# Microcontroller.net
KiCad netlist of a schematic drawn in Altium Designer
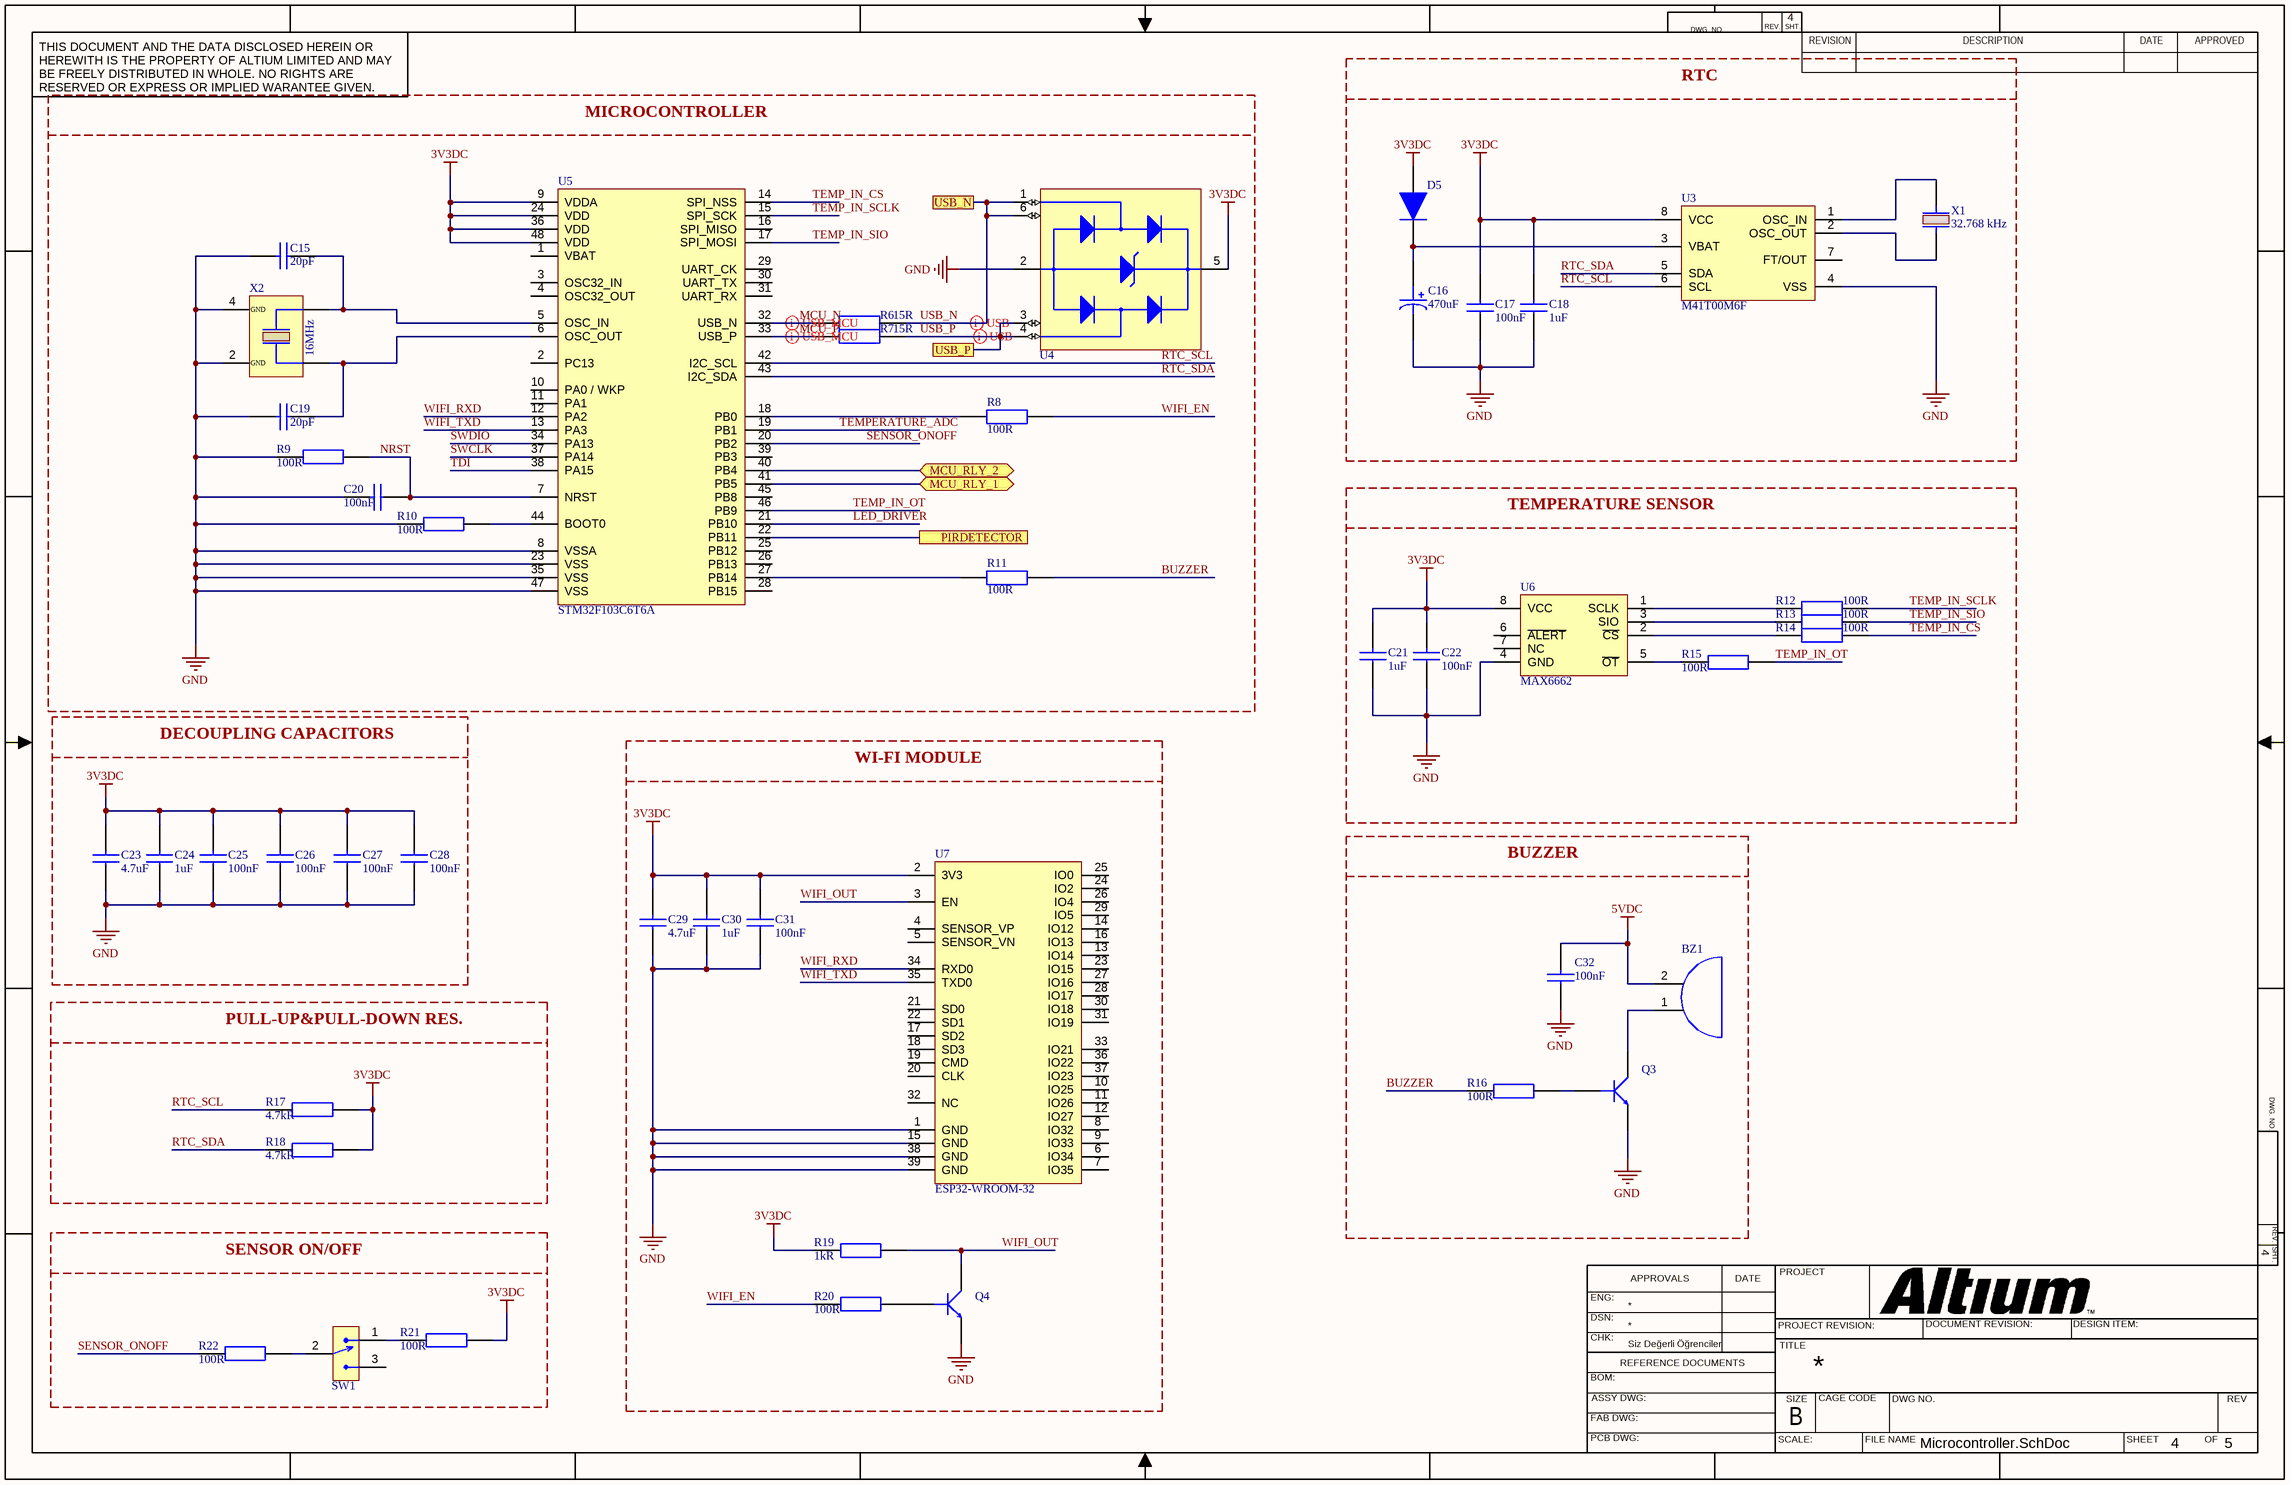
[diagram p0: Microcontroller.SchDoc]

(export (version "E")
  (design (tool "Eeschema 10.0.6"))
  (components
    (comp (ref "BZ1")
      (value "CMI-9605IC-0580T")
      (footprint "CMI-9605IC")
      (description "Buzzers Indicator, Internally Driven Magnetic 5V 30mA 2.7kHz 80dB @ 5V, 10cm Through Hole PC Pins")
      (fields (field (name "MANUFACTURER") "CUI Devices") (field (name "DESIGNED BY") "BERK"))
      (libsource (lib "UDEMY_Library") (part "CMI-9605IC-0580T"))
    )
    (comp (ref "C15")
      (value "CL10C200JB8NNNC")
      (footprint "CAP_0603")
      (description "CAP CER 20pF %5 0603 SMD")
      (fields
        (field (name "MANUFACTURER") "Samsung")
        (field (name "TOLERANCE") "5%")
        (field (name "CAPACITANCE") "20pF")
        (field (name "DESIGNED BY") "BERK")
      )
      (libsource (lib "UDEMY_Library") (part "CAP CER 20pF 0603"))
    )
    (comp (ref "C16")
      (value "ESH477M050AH4AA")
      (footprint "CAP_RADIAL_D10_P5")
      (description "CAP ALU ELEC 470uF 50V RADIAL")
      (fields
        (field (name "MANUFACTURER") "KEMET")
        (field (name "TOLERANCE") "20%")
        (field (name "CAPACITANCE") "470uF")
        (field (name "DESIGNED BY") "BERK")
      )
      (libsource (lib "UDEMY_Library") (part "CAP ALU ELEC 470uF 50V"))
    )
    (comp (ref "C17")
      (value "CL21B104KBCNNNC")
      (footprint "CAP_0805")
      (description "CAP CER 100nF %10 0805")
      (fields
        (field (name "MANUFACTURER") "Samsung")
        (field (name "TOLERANCE") "10%")
        (field (name "CAPACITANCE") "100nF")
        (field (name "DESIGNED BY") "BERK")
      )
      (libsource (lib "UDEMY_Library") (part "CAP CER 100nF 0805"))
    )
    (comp (ref "C18")
      (value "CL21B105KBFNNNE")
      (footprint "CAP_0805")
      (description "CAP CER 1uF %10 0805")
      (fields
        (field (name "MANUFACTURER") "Samsung")
        (field (name "TOLERANCE") "10%")
        (field (name "CAPACITANCE") "1uF")
        (field (name "DESIGNED BY") "BERK")
      )
      (libsource (lib "UDEMY_Library") (part "CAP CER 1uF 0805"))
    )
    (comp (ref "C19")
      (value "CL10C200JB8NNNC")
      (footprint "CAP_0603")
      (description "CAP CER 20pF %5 0603 SMD")
      (fields
        (field (name "MANUFACTURER") "Samsung")
        (field (name "TOLERANCE") "5%")
        (field (name "CAPACITANCE") "20pF")
        (field (name "DESIGNED BY") "BERK")
      )
      (libsource (lib "UDEMY_Library") (part "CAP CER 20pF 0603"))
    )
    (comp (ref "C20")
      (value "C0603C104K5RACTU")
      (footprint "CAP_0603")
      (description "CAP CER 100nF %10 0603 SMD")
      (fields
        (field (name "MANUFACTURER") "KEMET")
        (field (name "TOLERANCE") "10%")
        (field (name "CAPACITANCE") "100nF")
        (field (name "DESIGNED BY") "BERK")
      )
      (libsource (lib "UDEMY_Library") (part "CAP CER 100nF 0603"))
    )
    (comp (ref "C21")
      (value "CL21B105KBFNNNE")
      (footprint "CAP_0805")
      (description "CAP CER 1uF %10 0805")
      (fields
        (field (name "MANUFACTURER") "Samsung")
        (field (name "TOLERANCE") "10%")
        (field (name "CAPACITANCE") "1uF")
        (field (name "DESIGNED BY") "BERK")
      )
      (libsource (lib "UDEMY_Library") (part "CAP CER 1uF 0805"))
    )
    (comp (ref "C22")
      (value "CL21B104KBCNNNC")
      (footprint "CAP_0805")
      (description "CAP CER 100nF %10 0805")
      (fields
        (field (name "MANUFACTURER") "Samsung")
        (field (name "TOLERANCE") "10%")
        (field (name "CAPACITANCE") "100nF")
        (field (name "DESIGNED BY") "BERK")
      )
      (libsource (lib "UDEMY_Library") (part "CAP CER 100nF 0805"))
    )
    (comp (ref "C23")
      (value "CL21A475KAQNNNE")
      (footprint "CAP_0805")
      (description "CAP CER 4.7uF %10 0805")
      (fields
        (field (name "MANUFACTURER") "Samsung")
        (field (name "TOLERANCE") "10%")
        (field (name "CAPACITANCE") "4.7uF")
        (field (name "DESIGNED BY") "BERK")
      )
      (libsource (lib "UDEMY_Library") (part "CAP CER 4.7uF 0805"))
    )
    (comp (ref "C24")
      (value "CL21B105KBFNNNE")
      (footprint "CAP_0805")
      (description "CAP CER 1uF %10 0805")
      (fields
        (field (name "MANUFACTURER") "Samsung")
        (field (name "TOLERANCE") "10%")
        (field (name "CAPACITANCE") "1uF")
        (field (name "DESIGNED BY") "BERK")
      )
      (libsource (lib "UDEMY_Library") (part "CAP CER 1uF 0805"))
    )
    (comp (ref "C25")
      (value "C0603C104K5RACTU")
      (footprint "CAP_0603")
      (description "CAP CER 100nF %10 0603 SMD")
      (fields
        (field (name "MANUFACTURER") "KEMET")
        (field (name "TOLERANCE") "10%")
        (field (name "CAPACITANCE") "100nF")
        (field (name "DESIGNED BY") "BERK")
      )
      (libsource (lib "UDEMY_Library") (part "CAP CER 100nF 0603"))
    )
    (comp (ref "C26")
      (value "C0603C104K5RACTU")
      (footprint "CAP_0603")
      (description "CAP CER 100nF %10 0603 SMD")
      (fields
        (field (name "MANUFACTURER") "KEMET")
        (field (name "TOLERANCE") "10%")
        (field (name "CAPACITANCE") "100nF")
        (field (name "DESIGNED BY") "BERK")
      )
      (libsource (lib "UDEMY_Library") (part "CAP CER 100nF 0603"))
    )
    (comp (ref "C27")
      (value "C0603C104K5RACTU")
      (footprint "CAP_0603")
      (description "CAP CER 100nF %10 0603 SMD")
      (fields
        (field (name "MANUFACTURER") "KEMET")
        (field (name "TOLERANCE") "10%")
        (field (name "CAPACITANCE") "100nF")
        (field (name "DESIGNED BY") "BERK")
      )
      (libsource (lib "UDEMY_Library") (part "CAP CER 100nF 0603"))
    )
    (comp (ref "C28")
      (value "C0603C104K5RACTU")
      (footprint "CAP_0603")
      (description "CAP CER 100nF %10 0603 SMD")
      (fields
        (field (name "MANUFACTURER") "KEMET")
        (field (name "TOLERANCE") "10%")
        (field (name "CAPACITANCE") "100nF")
        (field (name "DESIGNED BY") "BERK")
      )
      (libsource (lib "UDEMY_Library") (part "CAP CER 100nF 0603"))
    )
    (comp (ref "C29")
      (value "CL21A475KAQNNNE")
      (footprint "CAP_0805")
      (description "CAP CER 4.7uF %10 0805")
      (fields
        (field (name "MANUFACTURER") "Samsung")
        (field (name "TOLERANCE") "10%")
        (field (name "CAPACITANCE") "4.7uF")
        (field (name "DESIGNED BY") "BERK")
      )
      (libsource (lib "UDEMY_Library") (part "CAP CER 4.7uF 0805"))
    )
    (comp (ref "C30")
      (value "CL21B105KBFNNNE")
      (footprint "CAP_0805")
      (description "CAP CER 1uF %10 0805")
      (fields
        (field (name "MANUFACTURER") "Samsung")
        (field (name "TOLERANCE") "10%")
        (field (name "CAPACITANCE") "1uF")
        (field (name "DESIGNED BY") "BERK")
      )
      (libsource (lib "UDEMY_Library") (part "CAP CER 1uF 0805"))
    )
    (comp (ref "C31")
      (value "CL21B104KBCNNNC")
      (footprint "CAP_0805")
      (description "CAP CER 100nF %10 0805")
      (fields
        (field (name "MANUFACTURER") "Samsung")
        (field (name "TOLERANCE") "10%")
        (field (name "CAPACITANCE") "100nF")
        (field (name "DESIGNED BY") "BERK")
      )
      (libsource (lib "UDEMY_Library") (part "CAP CER 100nF 0805"))
    )
    (comp (ref "C32")
      (value "CL21B104KBCNNNC")
      (footprint "CAP_0805")
      (description "CAP CER 100nF %10 0805")
      (fields
        (field (name "MANUFACTURER") "Samsung")
        (field (name "TOLERANCE") "10%")
        (field (name "CAPACITANCE") "100nF")
        (field (name "DESIGNED BY") "BERK")
      )
      (libsource (lib "UDEMY_Library") (part "CAP CER 100nF 0805"))
    )
    (comp (ref "D5")
      (value "1N4148WS")
      (footprint "SOD323F")
      (description "Diode, Single, 75 V, 150 mA, 1 V, 4 ns")
      (fields
        (field (name "MANUFACTURER") "ON Semiconductor / Fairchild")
        (field (name "DESIGNED BY") "BERK")
      )
      (libsource (lib "UDEMY_Library") (part "1N4148WS"))
    )
    (comp (ref "Q3")
      (value "MMBT3904-7-F")
      (footprint "SOT-23F")
      (description "Transistor General Purpose BJT NPN 40 Volt 0.2A Automotive 3-Pin SOT-23")
      (fields (field (name "MANUFACTURER") "Diodes Zetex") (field (name "DESIGNED BY") "BERK"))
      (libsource (lib "UDEMY_Library") (part "MMBT3904-7-F"))
    )
    (comp (ref "Q4")
      (value "MMBT3904-7-F")
      (footprint "SOT-23F")
      (description "Transistor General Purpose BJT NPN 40 Volt 0.2A Automotive 3-Pin SOT-23")
      (fields (field (name "MANUFACTURER") "Diodes Zetex") (field (name "DESIGNED BY") "BERK"))
      (libsource (lib "UDEMY_Library") (part "MMBT3904-7-F"))
    )
    (comp (ref "R6")
      (value "RC0603JR-0715RL")
      (footprint "RES_0603")
      (description "RES 15 %5 OHM 0603 SMD")
      (fields
        (field (name "MANUFACTURER") "Yageo")
        (field (name "TOLERANCE") "5%")
        (field (name "RESISTANCE") "15R")
        (field (name "DESIGNED BY") "BERK")
      )
      (libsource (lib "UDEMY_Library") (part "RES 15 OHM 0603"))
    )
    (comp (ref "R7")
      (value "RC0603JR-0715RL")
      (footprint "RES_0603")
      (description "RES 15 %5 OHM 0603 SMD")
      (fields
        (field (name "MANUFACTURER") "Yageo")
        (field (name "TOLERANCE") "5%")
        (field (name "RESISTANCE") "15R")
        (field (name "DESIGNED BY") "BERK")
      )
      (libsource (lib "UDEMY_Library") (part "RES 15 OHM 0603"))
    )
    (comp (ref "R8")
      (value "RC0603JR-07100RL")
      (footprint "RES_0603")
      (description "RES 100 %5 OHM 0603 SMD")
      (fields
        (field (name "MANUFACTURER") "Yageo")
        (field (name "TOLERANCE") "5%")
        (field (name "RESISTANCE") "100R")
        (field (name "DESIGNED BY") "BERK")
      )
      (libsource (lib "UDEMY_Library") (part "RES 100 OHM 0603"))
    )
    (comp (ref "R9")
      (value "RC0603JR-07100RL")
      (footprint "RES_0603")
      (description "RES 100 %5 OHM 0603 SMD")
      (fields
        (field (name "MANUFACTURER") "Yageo")
        (field (name "TOLERANCE") "5%")
        (field (name "RESISTANCE") "100R")
        (field (name "DESIGNED BY") "BERK")
      )
      (libsource (lib "UDEMY_Library") (part "RES 100 OHM 0603"))
    )
    (comp (ref "R10")
      (value "RC0603JR-07100RL")
      (footprint "RES_0603")
      (description "RES 100 %5 OHM 0603 SMD")
      (fields
        (field (name "MANUFACTURER") "Yageo")
        (field (name "TOLERANCE") "5%")
        (field (name "RESISTANCE") "100R")
        (field (name "DESIGNED BY") "BERK")
      )
      (libsource (lib "UDEMY_Library") (part "RES 100 OHM 0603"))
    )
    (comp (ref "R11")
      (value "RC0603JR-07100RL")
      (footprint "RES_0603")
      (description "RES 100 %5 OHM 0603 SMD")
      (fields
        (field (name "MANUFACTURER") "Yageo")
        (field (name "TOLERANCE") "5%")
        (field (name "RESISTANCE") "100R")
        (field (name "DESIGNED BY") "BERK")
      )
      (libsource (lib "UDEMY_Library") (part "RES 100 OHM 0603"))
    )
    (comp (ref "R12")
      (value "RC0603JR-07100RL")
      (footprint "RES_0603")
      (description "RES 100 %5 OHM 0603 SMD")
      (fields
        (field (name "MANUFACTURER") "Yageo")
        (field (name "TOLERANCE") "5%")
        (field (name "RESISTANCE") "100R")
        (field (name "DESIGNED BY") "BERK")
      )
      (libsource (lib "UDEMY_Library") (part "RES 100 OHM 0603"))
    )
    (comp (ref "R13")
      (value "RC0603JR-07100RL")
      (footprint "RES_0603")
      (description "RES 100 %5 OHM 0603 SMD")
      (fields
        (field (name "MANUFACTURER") "Yageo")
        (field (name "TOLERANCE") "5%")
        (field (name "RESISTANCE") "100R")
        (field (name "DESIGNED BY") "BERK")
      )
      (libsource (lib "UDEMY_Library") (part "RES 100 OHM 0603"))
    )
    (comp (ref "R14")
      (value "RC0603JR-07100RL")
      (footprint "RES_0603")
      (description "RES 100 %5 OHM 0603 SMD")
      (fields
        (field (name "MANUFACTURER") "Yageo")
        (field (name "TOLERANCE") "5%")
        (field (name "RESISTANCE") "100R")
        (field (name "DESIGNED BY") "BERK")
      )
      (libsource (lib "UDEMY_Library") (part "RES 100 OHM 0603"))
    )
    (comp (ref "R15")
      (value "RC0603JR-07100RL")
      (footprint "RES_0603")
      (description "RES 100 %5 OHM 0603 SMD")
      (fields
        (field (name "MANUFACTURER") "Yageo")
        (field (name "TOLERANCE") "5%")
        (field (name "RESISTANCE") "100R")
        (field (name "DESIGNED BY") "BERK")
      )
      (libsource (lib "UDEMY_Library") (part "RES 100 OHM 0603"))
    )
    (comp (ref "R16")
      (value "RC0603JR-07100RL")
      (footprint "RES_0603")
      (description "RES 100 %5 OHM 0603 SMD")
      (fields
        (field (name "MANUFACTURER") "Yageo")
        (field (name "TOLERANCE") "5%")
        (field (name "RESISTANCE") "100R")
        (field (name "DESIGNED BY") "BERK")
      )
      (libsource (lib "UDEMY_Library") (part "RES 100 OHM 0603"))
    )
    (comp (ref "R17")
      (value "RC0603JR-074K7L")
      (footprint "RES_0603")
      (description "RES 4K7 %5 OHM 0603 SMD")
      (fields
        (field (name "MANUFACTURER") "Yageo")
        (field (name "TOLERANCE") "5%")
        (field (name "RESISTANCE") "4.7kR")
        (field (name "DESIGNED BY") "BERK")
      )
      (libsource (lib "UDEMY_Library") (part "RES 4K7 OHM 0603"))
    )
    (comp (ref "R18")
      (value "RC0603JR-074K7L")
      (footprint "RES_0603")
      (description "RES 4K7 %5 OHM 0603 SMD")
      (fields
        (field (name "MANUFACTURER") "Yageo")
        (field (name "TOLERANCE") "5%")
        (field (name "RESISTANCE") "4.7kR")
        (field (name "DESIGNED BY") "BERK")
      )
      (libsource (lib "UDEMY_Library") (part "RES 4K7 OHM 0603"))
    )
    (comp (ref "R19")
      (value "RC0603FR-0710KL")
      (footprint "RES_0603")
      (description "RES 1K %1 OHM 0603 SMD")
      (fields
        (field (name "MANUFACTURER") "Yageo")
        (field (name "MANUFACTURER PART NUMBER") "RC0603JR-071KL")
        (field (name "RESISTANCE") "1kR")
        (field (name "DESIGNED BY") "BERK")
      )
      (libsource (lib "UDEMY_Library") (part "RES 1K OHM 0603"))
    )
    (comp (ref "R20")
      (value "RC0603JR-07100RL")
      (footprint "RES_0603")
      (description "RES 100 %5 OHM 0603 SMD")
      (fields
        (field (name "MANUFACTURER") "Yageo")
        (field (name "TOLERANCE") "5%")
        (field (name "RESISTANCE") "100R")
        (field (name "DESIGNED BY") "BERK")
      )
      (libsource (lib "UDEMY_Library") (part "RES 100 OHM 0603"))
    )
    (comp (ref "R21")
      (value "RC0603JR-07100RL")
      (footprint "RES_0603")
      (description "RES 100 %5 OHM 0603 SMD")
      (fields
        (field (name "MANUFACTURER") "Yageo")
        (field (name "TOLERANCE") "5%")
        (field (name "RESISTANCE") "100R")
        (field (name "DESIGNED BY") "BERK")
      )
      (libsource (lib "UDEMY_Library") (part "RES 100 OHM 0603"))
    )
    (comp (ref "R22")
      (value "RC0603JR-07100RL")
      (footprint "RES_0603")
      (description "RES 100 %5 OHM 0603 SMD")
      (fields
        (field (name "MANUFACTURER") "Yageo")
        (field (name "TOLERANCE") "5%")
        (field (name "RESISTANCE") "100R")
        (field (name "DESIGNED BY") "BERK")
      )
      (libsource (lib "") (part "RES 100 OHM 0603_1"))
    )
    (comp (ref "SW1")
      (value "EG1215AA")
      (footprint "EG1215AA")
      (description "Slide Switch, SPDT, 0.025A, 24V, SMD")
      (fields
        (field (name "MANUFACTURER") "E-Switch")
        (field (name "TOLERANCE") "4.95%")
        (field (name "DESIGNED BY") "BERK")
      )
      (libsource (lib "UDEMY_Library") (part "EG1215AA"))
    )
    (comp (ref "U3")
      (value "M41T00M6F")
      (footprint "SOIC8")
      (description "IC RTC CLK/CALENDAR I2C 8-SOIC")
      (fields (field (name "MANUFACTURER") "STMicroelectronics") (field (name "DESIGNED BY") "BERK"))
      (libsource (lib "UDEMY_Library") (part "M41T00M6F"))
    )
    (comp (ref "U4")
      (value "USBLC6-2SC6")
      (footprint "SOT23-6L")
      (description "TVS DIODE 5.25V 17V SOT23-6")
      (fields (field (name "MANUFACTURER") "STMicroelectronics") (field (name "DESIGNED BY") "BERK"))
      (libsource (lib "UDEMY_Library") (part "USB PROTECTION"))
    )
    (comp (ref "U5")
      (value "STM32F103C6T6A")
      (footprint "LQFP-48")
      (description "MCU 32-bit STM32F ARM Cortex M3 RISC 32KB Flash 2.5V/3.3V 48-Pin LQFP Tray")
      (fields (field (name "MANUFACTURER") "STMicroelectronics") (field (name "DESIGNED BY") "BERK"))
      (libsource (lib "UDEMY_Library") (part "STM32F103C6T6A"))
    )
    (comp (ref "U6")
      (value "MAX6662")
      (footprint "SOIC8")
      (description "SENSOR TEMPERATURE SPI 8SOIC")
      (fields
        (field (name "MANUFACTURER") "Maxim")
        (field (name "MANUFACTURER PART NUMBER") "MAX6662MSA+")
        (field (name "DESIGNED BY") "BERK")
      )
      (libsource (lib "UDEMY_Library") (part "MAX6662"))
    )
    (comp (ref "U7")
      (value "ESP32-WROOM-32")
      (footprint "ESP32-32")
      (description "SMD MODULE, ESP32-D0WDQ6, 32MBIT")
      (fields (field (name "MANUFACTURER") "Espressif Systems") (field (name "DESIGNED BY") "BERK"))
      (libsource (lib "UDEMY_Library") (part "ESP32-WROOM-32"))
    )
    (comp (ref "X1")
      (value "ABS05-32.768KHZ-T")
      (footprint "ABS05")
      (description "Crystal, 32.768 kHz, SMD, 1.6mm x 1mm, 12.5 pF, 20 ppm, ABS05 Series")
      (fields
        (field (name "MANUFACTURER") "Abracon")
        (field (name "TOLERANCE") "20ppm")
        (field (name "OPERATING FREQUENCY") "32.768 kHz")
        (field (name "DESIGNED BY") "BERK")
      )
      (libsource (lib "UDEMY_Library") (part "CRYSTAL 32768kHZ"))
    )
    (comp (ref "X2")
      (value "ECS-160-20-30B-TR")
      (footprint "ECS")
      (description "CRYSTAL 16.0000MHZ 20PF SMD")
      (fields
        (field (name "MANUFACTURER") "ECS International")
        (field (name "TOLERANCE") "50ppm")
        (field (name "FREQUENCY") "16MHz")
        (field (name "DESIGNED BY") "BERK")
      )
      (libsource (lib "UDEMY_Library") (part "CRYSTAL 16MHz"))
    )
  )
  (nets
    (net (code "1") (name "/BUZZER") (class "Default")
      (node (ref "R11") (pin "2") (pinfunction "2_2") (pintype "passive"))
      (node (ref "R16") (pin "1") (pinfunction "1_1") (pintype "passive"))
    )
    (net (code "2") (name "/LED_DRIVER") (class "Default")
      (node (ref "U5") (pin "21") (pinfunction "PB10_21") (pintype "passive"))
    )
    (net (code "3") (name "/MCU_N") (class "Default")
      (node (ref "R6") (pin "1") (pinfunction "1_1") (pintype "passive"))
      (node (ref "U5") (pin "32") (pinfunction "USB_N_32") (pintype "passive"))
    )
    (net (code "4") (name "/MCU_P") (class "Default")
      (node (ref "R7") (pin "1") (pinfunction "1_1") (pintype "passive"))
      (node (ref "U5") (pin "33") (pinfunction "USB_P_33") (pintype "passive"))
    )
    (net (code "5") (name "/MCU_RLY_1") (class "Default")
      (node (ref "U5") (pin "41") (pinfunction "PB5_41") (pintype "passive"))
    )
    (net (code "6") (name "/MCU_RLY_2") (class "Default")
      (node (ref "U5") (pin "40") (pinfunction "PB4_40") (pintype "passive"))
    )
    (net (code "7") (name "/NRST") (class "Default")
      (node (ref "C20") (pin "1") (pinfunction "1_1") (pintype "passive"))
      (node (ref "R9") (pin "2") (pinfunction "2_2") (pintype "passive"))
      (node (ref "U5") (pin "7") (pinfunction "NRST_7") (pintype "passive"))
    )
    (net (code "8") (name "/PIRDETECTOR") (class "Default")
      (node (ref "U5") (pin "22") (pinfunction "PB11_22") (pintype "passive"))
    )
    (net (code "9") (name "/RTC_SCL") (class "Default")
      (node (ref "R17") (pin "1") (pinfunction "1_1") (pintype "passive"))
      (node (ref "U3") (pin "6") (pinfunction "SCL_6") (pintype "passive"))
      (node (ref "U5") (pin "42") (pinfunction "I2C_SCL_42") (pintype "passive"))
    )
    (net (code "10") (name "/RTC_SDA") (class "Default")
      (node (ref "R18") (pin "1") (pinfunction "1_1") (pintype "passive"))
      (node (ref "U3") (pin "5") (pinfunction "SDA_5") (pintype "passive"))
      (node (ref "U5") (pin "43") (pinfunction "I2C_SDA_43") (pintype "passive"))
    )
    (net (code "11") (name "/SENSOR_ONOFF") (class "Default")
      (node (ref "R22") (pin "2") (pinfunction "2_2") (pintype "passive"))
      (node (ref "U5") (pin "20") (pinfunction "PB2_20") (pintype "passive"))
    )
    (net (code "12") (name "/SWCLK") (class "Default")
      (node (ref "U5") (pin "37") (pinfunction "PA14_37") (pintype "passive"))
    )
    (net (code "13") (name "/SWDIO") (class "Default")
      (node (ref "U5") (pin "34") (pinfunction "PA13_34") (pintype "passive"))
    )
    (net (code "14") (name "/TDI") (class "Default")
      (node (ref "U5") (pin "38") (pinfunction "PA15_38") (pintype "passive"))
    )
    (net (code "15") (name "/TEMPERATURE_ADC") (class "Default")
      (node (ref "U5") (pin "19") (pinfunction "PB1_19") (pintype "passive"))
    )
    (net (code "16") (name "/TEMP_IN_CS") (class "Default")
      (node (ref "R14") (pin "2") (pinfunction "2_2") (pintype "passive"))
      (node (ref "U5") (pin "14") (pinfunction "SPI_NSS_14") (pintype "passive"))
    )
    (net (code "17") (name "/TEMP_IN_OT") (class "Default")
      (node (ref "R15") (pin "2") (pinfunction "2_2") (pintype "passive"))
      (node (ref "U5") (pin "46") (pinfunction "PB9_46") (pintype "passive"))
    )
    (net (code "18") (name "/TEMP_IN_SCLK") (class "Default")
      (node (ref "R12") (pin "2") (pinfunction "2_2") (pintype "passive"))
      (node (ref "U5") (pin "15") (pinfunction "SPI_SCK_15") (pintype "passive"))
    )
    (net (code "19") (name "/TEMP_IN_SIO") (class "Default")
      (node (ref "R13") (pin "2") (pinfunction "2_2") (pintype "passive"))
      (node (ref "U5") (pin "17") (pinfunction "SPI_MOSI_17") (pintype "passive"))
    )
    (net (code "20") (name "/USB_N") (class "Default")
      (node (ref "R6") (pin "2") (pinfunction "2_2") (pintype "passive"))
      (node (ref "U4") (pin "1") (pinfunction "I/O1_1") (pintype "bidirectional"))
      (node (ref "U4") (pin "6") (pinfunction "I/O1_6") (pintype "bidirectional"))
    )
    (net (code "21") (name "/USB_P") (class "Default")
      (node (ref "R7") (pin "2") (pinfunction "2_2") (pintype "passive"))
      (node (ref "U4") (pin "3") (pinfunction "I/O2_3") (pintype "bidirectional"))
      (node (ref "U4") (pin "4") (pinfunction "I/O2_4") (pintype "bidirectional"))
    )
    (net (code "22") (name "/WIFI_EN") (class "Default")
      (node (ref "R20") (pin "1") (pinfunction "1_1") (pintype "passive"))
      (node (ref "R8") (pin "2") (pinfunction "2_2") (pintype "passive"))
    )
    (net (code "23") (name "/WIFI_OUT") (class "Default")
      (node (ref "Q4") (pin "3") (pinfunction "C_3") (pintype "power_in"))
      (node (ref "R19") (pin "1") (pinfunction "1_1") (pintype "passive"))
      (node (ref "U7") (pin "3") (pinfunction "EN_3") (pintype "passive"))
    )
    (net (code "24") (name "/WIFI_RXD") (class "Default")
      (node (ref "U5") (pin "12") (pinfunction "PA2_12") (pintype "passive"))
      (node (ref "U7") (pin "34") (pinfunction "RXD0_34") (pintype "passive"))
    )
    (net (code "25") (name "/WIFI_TXD") (class "Default")
      (node (ref "U5") (pin "13") (pinfunction "PA3_13") (pintype "passive"))
      (node (ref "U7") (pin "35") (pinfunction "TXD0_35") (pintype "passive"))
    )
    (net (code "26") (name "3V3DC") (class "Default")
      (node (ref "C17") (pin "2") (pinfunction "2_2") (pintype "passive"))
      (node (ref "C18") (pin "2") (pinfunction "2_2") (pintype "passive"))
      (node (ref "C21") (pin "2") (pinfunction "2_2") (pintype "passive"))
      (node (ref "C22") (pin "2") (pinfunction "2_2") (pintype "passive"))
      (node (ref "C23") (pin "2") (pinfunction "2_2") (pintype "passive"))
      (node (ref "C24") (pin "2") (pinfunction "2_2") (pintype "passive"))
      (node (ref "C25") (pin "2") (pinfunction "2_2") (pintype "passive"))
      (node (ref "C26") (pin "2") (pinfunction "2_2") (pintype "passive"))
      (node (ref "C27") (pin "2") (pinfunction "2_2") (pintype "passive"))
      (node (ref "C28") (pin "2") (pinfunction "2_2") (pintype "passive"))
      (node (ref "C29") (pin "2") (pinfunction "2_2") (pintype "passive"))
      (node (ref "C30") (pin "2") (pinfunction "2_2") (pintype "passive"))
      (node (ref "C31") (pin "2") (pinfunction "2_2") (pintype "passive"))
      (node (ref "D5") (pin "2") (pinfunction "2_2") (pintype "power_in"))
      (node (ref "R17") (pin "2") (pinfunction "2_2") (pintype "passive"))
      (node (ref "R18") (pin "2") (pinfunction "2_2") (pintype "passive"))
      (node (ref "R19") (pin "2") (pinfunction "2_2") (pintype "passive"))
      (node (ref "R21") (pin "2") (pinfunction "2_2") (pintype "passive"))
      (node (ref "U3") (pin "8") (pinfunction "VCC_8") (pintype "passive"))
      (node (ref "U4") (pin "5") (pinfunction "VBUS_5") (pintype "power_in"))
      (node (ref "U5") (pin "24") (pinfunction "VDD_24") (pintype "passive"))
      (node (ref "U5") (pin "36") (pinfunction "VDD_36") (pintype "passive"))
      (node (ref "U5") (pin "48") (pinfunction "VDD_48") (pintype "passive"))
      (node (ref "U5") (pin "9") (pinfunction "VDDA_9") (pintype "passive"))
      (node (ref "U6") (pin "8") (pinfunction "VCC_8") (pintype "passive"))
      (node (ref "U7") (pin "2") (pinfunction "3V3_2") (pintype "passive"))
    )
    (net (code "27") (name "5VDC") (class "Default")
      (node (ref "BZ1") (pin "2") (pinfunction "2_2") (pintype "passive"))
      (node (ref "C32") (pin "2") (pinfunction "2_2") (pintype "passive"))
    )
    (net (code "28") (name "GND") (class "Default")
      (node (ref "C15") (pin "2") (pinfunction "2_2") (pintype "passive"))
      (node (ref "C16") (pin "2") (pinfunction "2_2") (pintype "passive"))
      (node (ref "C17") (pin "1") (pinfunction "1_1") (pintype "passive"))
      (node (ref "C18") (pin "1") (pinfunction "1_1") (pintype "passive"))
      (node (ref "C19") (pin "2") (pinfunction "2_2") (pintype "passive"))
      (node (ref "C20") (pin "2") (pinfunction "2_2") (pintype "passive"))
      (node (ref "C21") (pin "1") (pinfunction "1_1") (pintype "passive"))
      (node (ref "C22") (pin "1") (pinfunction "1_1") (pintype "passive"))
      (node (ref "C23") (pin "1") (pinfunction "1_1") (pintype "passive"))
      (node (ref "C24") (pin "1") (pinfunction "1_1") (pintype "passive"))
      (node (ref "C25") (pin "1") (pinfunction "1_1") (pintype "passive"))
      (node (ref "C26") (pin "1") (pinfunction "1_1") (pintype "passive"))
      (node (ref "C27") (pin "1") (pinfunction "1_1") (pintype "passive"))
      (node (ref "C28") (pin "1") (pinfunction "1_1") (pintype "passive"))
      (node (ref "C29") (pin "1") (pinfunction "1_1") (pintype "passive"))
      (node (ref "C30") (pin "1") (pinfunction "1_1") (pintype "passive"))
      (node (ref "C31") (pin "1") (pinfunction "1_1") (pintype "passive"))
      (node (ref "C32") (pin "1") (pinfunction "1_1") (pintype "passive"))
      (node (ref "Q3") (pin "2") (pinfunction "E_2") (pintype "power_in"))
      (node (ref "Q4") (pin "2") (pinfunction "E_2") (pintype "power_in"))
      (node (ref "R10") (pin "1") (pinfunction "1_1") (pintype "passive"))
      (node (ref "R9") (pin "1") (pinfunction "1_1") (pintype "passive"))
      (node (ref "U3") (pin "4") (pinfunction "VSS_4") (pintype "passive"))
      (node (ref "U4") (pin "2") (pinfunction "GND_2") (pintype "power_in"))
      (node (ref "U5") (pin "23") (pinfunction "VSS_23") (pintype "passive"))
      (node (ref "U5") (pin "35") (pinfunction "VSS_35") (pintype "passive"))
      (node (ref "U5") (pin "47") (pinfunction "VSS_47") (pintype "passive"))
      (node (ref "U5") (pin "8") (pinfunction "VSSA_8") (pintype "passive"))
      (node (ref "U6") (pin "4") (pinfunction "GND_4") (pintype "passive"))
      (node (ref "U7") (pin "1") (pinfunction "GND_1") (pintype "passive"))
      (node (ref "U7") (pin "15") (pinfunction "GND_15") (pintype "passive"))
      (node (ref "U7") (pin "38") (pinfunction "GND_38") (pintype "passive"))
      (node (ref "U7") (pin "39") (pinfunction "GND_39") (pintype "passive"))
      (node (ref "X2") (pin "2") (pinfunction "GND_2") (pintype "passive"))
      (node (ref "X2") (pin "4") (pinfunction "GND_4") (pintype "passive"))
    )
    (net (code "29") (name "Net-(Q3-B)") (class "Default")
      (node (ref "Q3") (pin "1") (pinfunction "B_1") (pintype "power_in"))
      (node (ref "R16") (pin "2") (pinfunction "2_2") (pintype "passive"))
    )
    (net (code "30") (name "Net-(Q3-C)") (class "Default")
      (node (ref "BZ1") (pin "1") (pinfunction "1_1") (pintype "passive"))
      (node (ref "Q3") (pin "3") (pinfunction "C_3") (pintype "power_in"))
    )
    (net (code "31") (name "Net-(Q4-B)") (class "Default")
      (node (ref "Q4") (pin "1") (pinfunction "B_1") (pintype "power_in"))
      (node (ref "R20") (pin "2") (pinfunction "2_2") (pintype "passive"))
    )
    (net (code "32") (name "Net-(R21-Pad1)") (class "Default")
      (node (ref "R21") (pin "1") (pinfunction "1_1") (pintype "passive"))
      (node (ref "SW1") (pin "1") (pinfunction "1_1") (pintype "passive"))
    )
    (net (code "33") (name "Net-(R22-Pad1)") (class "Default")
      (node (ref "R22") (pin "1") (pinfunction "1_1") (pintype "passive"))
      (node (ref "SW1") (pin "2") (pinfunction "2_2") (pintype "passive"))
    )
    (net (code "34") (name "Net-(U3-OSC_IN)") (class "Default")
      (node (ref "U3") (pin "1") (pinfunction "OSC_IN_1") (pintype "passive"))
      (node (ref "X1") (pin "2") (pinfunction "2_2") (pintype "passive"))
    )
    (net (code "35") (name "Net-(U3-OSC_OUT)") (class "Default")
      (node (ref "U3") (pin "2") (pinfunction "OSC_OUT_2") (pintype "passive"))
      (node (ref "X1") (pin "1") (pinfunction "1_1") (pintype "passive"))
    )
    (net (code "36") (name "Net-(U3-VBAT)") (class "Default")
      (node (ref "C16") (pin "1") (pinfunction "1_1") (pintype "passive"))
      (node (ref "D5") (pin "1") (pinfunction "1_1") (pintype "power_in"))
      (node (ref "U3") (pin "3") (pinfunction "VBAT_3") (pintype "passive"))
    )
    (net (code "37") (name "Net-(U5-BOOT0)") (class "Default")
      (node (ref "R10") (pin "2") (pinfunction "2_2") (pintype "passive"))
      (node (ref "U5") (pin "44") (pinfunction "BOOT0_44") (pintype "passive"))
    )
    (net (code "38") (name "Net-(U5-OSC_IN)") (class "Default")
      (node (ref "C15") (pin "1") (pinfunction "1_1") (pintype "passive"))
      (node (ref "U5") (pin "5") (pinfunction "OSC_IN_5") (pintype "passive"))
      (node (ref "X2") (pin "3") (pinfunction "3_3") (pintype "passive"))
    )
    (net (code "39") (name "Net-(U5-OSC_OUT)") (class "Default")
      (node (ref "C19") (pin "1") (pinfunction "1_1") (pintype "passive"))
      (node (ref "U5") (pin "6") (pinfunction "OSC_OUT_6") (pintype "passive"))
      (node (ref "X2") (pin "1") (pinfunction "1_1") (pintype "passive"))
    )
    (net (code "40") (name "Net-(U5-PB0)") (class "Default")
      (node (ref "R8") (pin "1") (pinfunction "1_1") (pintype "passive"))
      (node (ref "U5") (pin "18") (pinfunction "PB0_18") (pintype "passive"))
    )
    (net (code "41") (name "Net-(U5-PB14)") (class "Default")
      (node (ref "R11") (pin "1") (pinfunction "1_1") (pintype "passive"))
      (node (ref "U5") (pin "27") (pinfunction "PB14_27") (pintype "passive"))
    )
    (net (code "42") (name "Net-(U6-SCLK)") (class "Default")
      (node (ref "R12") (pin "1") (pinfunction "1_1") (pintype "passive"))
      (node (ref "U6") (pin "1") (pinfunction "SCLK_1") (pintype "passive"))
    )
    (net (code "43") (name "Net-(U6-SIO)") (class "Default")
      (node (ref "R13") (pin "1") (pinfunction "1_1") (pintype "passive"))
      (node (ref "U6") (pin "3") (pinfunction "SIO_3") (pintype "passive"))
    )
    (net (code "44") (name "Net-(U6-~{CS})") (class "Default")
      (node (ref "R14") (pin "1") (pinfunction "1_1") (pintype "passive"))
      (node (ref "U6") (pin "2") (pinfunction "~{CS}_2") (pintype "passive"))
    )
    (net (code "45") (name "Net-(U6-~{OT})") (class "Default")
      (node (ref "R15") (pin "1") (pinfunction "1_1") (pintype "passive"))
      (node (ref "U6") (pin "5") (pinfunction "~{OT}_5") (pintype "passive"))
    )
    (net (code "46") (name "unconnected-(SW1-Pad3)") (class "Default")
      (node (ref "SW1") (pin "3") (pinfunction "3_3") (pintype "passive"))
    )
    (net (code "47") (name "unconnected-(U3-FT{slash}OUT-Pad7)") (class "Default")
      (node (ref "U3") (pin "7") (pinfunction "FT/OUT_7") (pintype "passive"))
    )
    (net (code "48") (name "unconnected-(U5-OSC32_IN-Pad3)") (class "Default")
      (node (ref "U5") (pin "3") (pinfunction "OSC32_IN_3") (pintype "passive"))
    )
    (net (code "49") (name "unconnected-(U5-OSC32_OUT-Pad4)") (class "Default")
      (node (ref "U5") (pin "4") (pinfunction "OSC32_OUT_4") (pintype "passive"))
    )
    (net (code "50") (name "unconnected-(U5-PA0_{slash}_WKP-Pad10)") (class "Default")
      (node (ref "U5") (pin "10") (pinfunction "PA0_/_WKP_10") (pintype "passive"))
    )
    (net (code "51") (name "unconnected-(U5-PA1-Pad11)") (class "Default")
      (node (ref "U5") (pin "11") (pinfunction "PA1_11") (pintype "passive"))
    )
    (net (code "52") (name "unconnected-(U5-PB3-Pad39)") (class "Default")
      (node (ref "U5") (pin "39") (pinfunction "PB3_39") (pintype "passive"))
    )
    (net (code "53") (name "unconnected-(U5-PB8-Pad45)") (class "Default")
      (node (ref "U5") (pin "45") (pinfunction "PB8_45") (pintype "passive"))
    )
    (net (code "54") (name "unconnected-(U5-PB12-Pad25)") (class "Default")
      (node (ref "U5") (pin "25") (pinfunction "PB12_25") (pintype "passive"))
    )
    (net (code "55") (name "unconnected-(U5-PB13-Pad26)") (class "Default")
      (node (ref "U5") (pin "26") (pinfunction "PB13_26") (pintype "passive"))
    )
    (net (code "56") (name "unconnected-(U5-PB15-Pad28)") (class "Default")
      (node (ref "U5") (pin "28") (pinfunction "PB15_28") (pintype "passive"))
    )
    (net (code "57") (name "unconnected-(U5-PC13-Pad2)") (class "Default")
      (node (ref "U5") (pin "2") (pinfunction "PC13_2") (pintype "passive"))
    )
    (net (code "58") (name "unconnected-(U5-SPI_MISO-Pad16)") (class "Default")
      (node (ref "U5") (pin "16") (pinfunction "SPI_MISO_16") (pintype "passive"))
    )
    (net (code "59") (name "unconnected-(U5-UART_CK-Pad29)") (class "Default")
      (node (ref "U5") (pin "29") (pinfunction "UART_CK_29") (pintype "passive"))
    )
    (net (code "60") (name "unconnected-(U5-UART_RX-Pad31)") (class "Default")
      (node (ref "U5") (pin "31") (pinfunction "UART_RX_31") (pintype "passive"))
    )
    (net (code "61") (name "unconnected-(U5-UART_TX-Pad30)") (class "Default")
      (node (ref "U5") (pin "30") (pinfunction "UART_TX_30") (pintype "passive"))
    )
    (net (code "62") (name "unconnected-(U5-VBAT-Pad1)") (class "Default")
      (node (ref "U5") (pin "1") (pinfunction "VBAT_1") (pintype "passive"))
    )
    (net (code "63") (name "unconnected-(U6-NC-Pad7)") (class "Default")
      (node (ref "U6") (pin "7") (pinfunction "NC_7") (pintype "passive"))
    )
    (net (code "64") (name "unconnected-(U6-~{ALERT}-Pad6)") (class "Default")
      (node (ref "U6") (pin "6") (pinfunction "~{ALERT}_6") (pintype "passive"))
    )
    (net (code "65") (name "unconnected-(U7-CLK-Pad20)") (class "Default")
      (node (ref "U7") (pin "20") (pinfunction "CLK_20") (pintype "passive"))
    )
    (net (code "66") (name "unconnected-(U7-CMD-Pad19)") (class "Default")
      (node (ref "U7") (pin "19") (pinfunction "CMD_19") (pintype "passive"))
    )
    (net (code "67") (name "unconnected-(U7-IO0-Pad25)") (class "Default")
      (node (ref "U7") (pin "25") (pinfunction "IO0_25") (pintype "passive"))
    )
    (net (code "68") (name "unconnected-(U7-IO2-Pad24)") (class "Default")
      (node (ref "U7") (pin "24") (pinfunction "IO2_24") (pintype "passive"))
    )
    (net (code "69") (name "unconnected-(U7-IO4-Pad26)") (class "Default")
      (node (ref "U7") (pin "26") (pinfunction "IO4_26") (pintype "passive"))
    )
    (net (code "70") (name "unconnected-(U7-IO5-Pad29)") (class "Default")
      (node (ref "U7") (pin "29") (pinfunction "IO5_29") (pintype "passive"))
    )
    (net (code "71") (name "unconnected-(U7-IO12-Pad14)") (class "Default")
      (node (ref "U7") (pin "14") (pinfunction "IO12_14") (pintype "passive"))
    )
    (net (code "72") (name "unconnected-(U7-IO13-Pad16)") (class "Default")
      (node (ref "U7") (pin "16") (pinfunction "IO13_16") (pintype "passive"))
    )
    (net (code "73") (name "unconnected-(U7-IO14-Pad13)") (class "Default")
      (node (ref "U7") (pin "13") (pinfunction "IO14_13") (pintype "passive"))
    )
    (net (code "74") (name "unconnected-(U7-IO15-Pad23)") (class "Default")
      (node (ref "U7") (pin "23") (pinfunction "IO15_23") (pintype "passive"))
    )
    (net (code "75") (name "unconnected-(U7-IO16-Pad27)") (class "Default")
      (node (ref "U7") (pin "27") (pinfunction "IO16_27") (pintype "passive"))
    )
    (net (code "76") (name "unconnected-(U7-IO17-Pad28)") (class "Default")
      (node (ref "U7") (pin "28") (pinfunction "IO17_28") (pintype "passive"))
    )
    (net (code "77") (name "unconnected-(U7-IO18-Pad30)") (class "Default")
      (node (ref "U7") (pin "30") (pinfunction "IO18_30") (pintype "passive"))
    )
    (net (code "78") (name "unconnected-(U7-IO19-Pad31)") (class "Default")
      (node (ref "U7") (pin "31") (pinfunction "IO19_31") (pintype "passive"))
    )
    (net (code "79") (name "unconnected-(U7-IO21-Pad33)") (class "Default")
      (node (ref "U7") (pin "33") (pinfunction "IO21_33") (pintype "passive"))
    )
    (net (code "80") (name "unconnected-(U7-IO22-Pad36)") (class "Default")
      (node (ref "U7") (pin "36") (pinfunction "IO22_36") (pintype "passive"))
    )
    (net (code "81") (name "unconnected-(U7-IO23-Pad37)") (class "Default")
      (node (ref "U7") (pin "37") (pinfunction "IO23_37") (pintype "passive"))
    )
    (net (code "82") (name "unconnected-(U7-IO25-Pad10)") (class "Default")
      (node (ref "U7") (pin "10") (pinfunction "IO25_10") (pintype "passive"))
    )
    (net (code "83") (name "unconnected-(U7-IO26-Pad11)") (class "Default")
      (node (ref "U7") (pin "11") (pinfunction "IO26_11") (pintype "passive"))
    )
    (net (code "84") (name "unconnected-(U7-IO27-Pad12)") (class "Default")
      (node (ref "U7") (pin "12") (pinfunction "IO27_12") (pintype "passive"))
    )
    (net (code "85") (name "unconnected-(U7-IO32-Pad8)") (class "Default")
      (node (ref "U7") (pin "8") (pinfunction "IO32_8") (pintype "passive"))
    )
    (net (code "86") (name "unconnected-(U7-IO33-Pad9)") (class "Default")
      (node (ref "U7") (pin "9") (pinfunction "IO33_9") (pintype "passive"))
    )
    (net (code "87") (name "unconnected-(U7-IO34-Pad6)") (class "Default")
      (node (ref "U7") (pin "6") (pinfunction "IO34_6") (pintype "passive"))
    )
    (net (code "88") (name "unconnected-(U7-IO35-Pad7)") (class "Default")
      (node (ref "U7") (pin "7") (pinfunction "IO35_7") (pintype "passive"))
    )
    (net (code "89") (name "unconnected-(U7-NC-Pad32)") (class "Default")
      (node (ref "U7") (pin "32") (pinfunction "NC_32") (pintype "passive"))
    )
    (net (code "90") (name "unconnected-(U7-SD0-Pad21)") (class "Default")
      (node (ref "U7") (pin "21") (pinfunction "SD0_21") (pintype "passive"))
    )
    (net (code "91") (name "unconnected-(U7-SD1-Pad22)") (class "Default")
      (node (ref "U7") (pin "22") (pinfunction "SD1_22") (pintype "passive"))
    )
    (net (code "92") (name "unconnected-(U7-SD2-Pad17)") (class "Default")
      (node (ref "U7") (pin "17") (pinfunction "SD2_17") (pintype "passive"))
    )
    (net (code "93") (name "unconnected-(U7-SD3-Pad18)") (class "Default")
      (node (ref "U7") (pin "18") (pinfunction "SD3_18") (pintype "passive"))
    )
    (net (code "94") (name "unconnected-(U7-SENSOR_VN-Pad5)") (class "Default")
      (node (ref "U7") (pin "5") (pinfunction "SENSOR_VN_5") (pintype "passive"))
    )
    (net (code "95") (name "unconnected-(U7-SENSOR_VP-Pad4)") (class "Default")
      (node (ref "U7") (pin "4") (pinfunction "SENSOR_VP_4") (pintype "passive"))
    )
  )
)
